# spot-welding.net
KiCad netlist of a schematic drawn in EAGLE
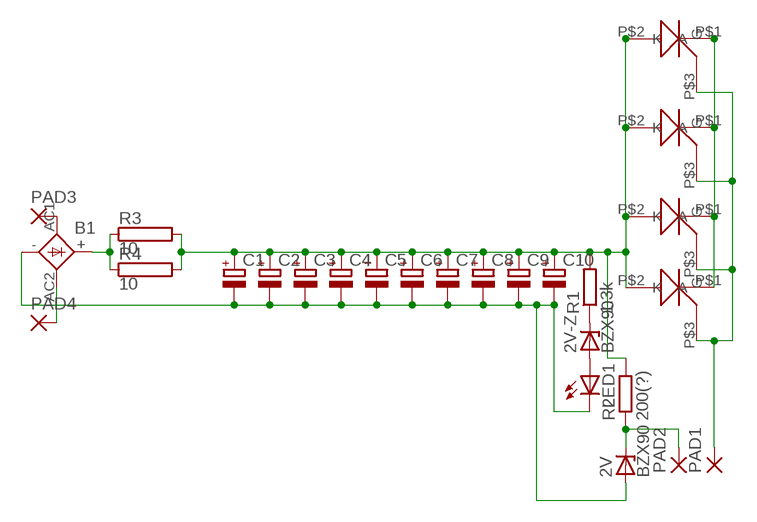
[diagram p0: schematic, sheet 1]

(export (version "E")
  (design (tool "Eeschema 10.0.6"))
  (components
    (comp (ref "2V")
      (value "BZX90")
      (footprint "eagle-import:DO34Z7")
      (libsource (lib "eagle-import") (part "BZX90"))
    )
    (comp (ref "2V-Z")
      (value "BZX90")
      (footprint "eagle-import:DO34Z7")
      (libsource (lib "eagle-import") (part "BZX90"))
    )
    (comp (ref "B1")
      (value "KBU")
      (footprint "eagle-import:KBU")
      (libsource (lib "eagle-import") (part "KBU"))
    )
    (comp (ref "C1")
      (value "CPOL-EUE10-30")
      (footprint "eagle-import:EB30D")
      (libsource (lib "eagle-import") (part "CPOL-EUE10-30"))
    )
    (comp (ref "C2")
      (value "CPOL-EUE10-30")
      (footprint "eagle-import:EB30D")
      (libsource (lib "eagle-import") (part "CPOL-EUE10-30"))
    )
    (comp (ref "C3")
      (value "CPOL-EUE10-30")
      (footprint "eagle-import:EB30D")
      (libsource (lib "eagle-import") (part "CPOL-EUE10-30"))
    )
    (comp (ref "C4")
      (value "CPOL-EUE10-30")
      (footprint "eagle-import:EB30D")
      (libsource (lib "eagle-import") (part "CPOL-EUE10-30"))
    )
    (comp (ref "C5")
      (value "CPOL-EUE10-30")
      (footprint "eagle-import:EB30D")
      (libsource (lib "eagle-import") (part "CPOL-EUE10-30"))
    )
    (comp (ref "C6")
      (value "CPOL-EUE10-30")
      (footprint "eagle-import:EB30D")
      (libsource (lib "eagle-import") (part "CPOL-EUE10-30"))
    )
    (comp (ref "C7")
      (value "CPOL-EUE10-30")
      (footprint "eagle-import:EB30D")
      (libsource (lib "eagle-import") (part "CPOL-EUE10-30"))
    )
    (comp (ref "C8")
      (value "CPOL-EUE10-30")
      (footprint "eagle-import:EB30D")
      (libsource (lib "eagle-import") (part "CPOL-EUE10-30"))
    )
    (comp (ref "C9")
      (value "CPOL-EUE10-30")
      (footprint "eagle-import:EB30D")
      (libsource (lib "eagle-import") (part "CPOL-EUE10-30"))
    )
    (comp (ref "C10")
      (value "CPOL-EUE10-30")
      (footprint "eagle-import:EB30D")
      (libsource (lib "eagle-import") (part "CPOL-EUE10-30"))
    )
    (comp (ref "LED1")
      (value "LED3MM")
      (footprint "eagle-import:LED3MM")
      (libsource (lib "eagle-import") (part "LED3MM"))
    )
    (comp (ref "PAD1")
      (value "3,17/1,1")
      (footprint "eagle-import:3,17_1,1")
      (libsource (lib "eagle-import") (part "3,17/1,1"))
    )
    (comp (ref "PAD2")
      (value "3,17/1,1")
      (footprint "eagle-import:3,17_1,1")
      (libsource (lib "eagle-import") (part "3,17/1,1"))
    )
    (comp (ref "PAD3")
      (value "3,17/1,1")
      (footprint "eagle-import:3,17_1,1")
      (libsource (lib "eagle-import") (part "3,17/1,1"))
    )
    (comp (ref "PAD4")
      (value "3,17/1,1")
      (footprint "eagle-import:3,17_1,1")
      (libsource (lib "eagle-import") (part "3,17/1,1"))
    )
    (comp (ref "R1")
      (value "1.3k")
      (footprint "eagle-import:0204_7")
      (libsource (lib "eagle-import") (part "R-EU_0204/7"))
    )
    (comp (ref "R2")
      (value "200(?)")
      (footprint "eagle-import:0204_7")
      (libsource (lib "eagle-import") (part "R-EU_0204/7"))
    )
    (comp (ref "R3")
      (value "10")
      (footprint "eagle-import:KH214R-8")
      (libsource (lib "eagle-import") (part "RKH214-8R"))
    )
    (comp (ref "R4")
      (value "10")
      (footprint "eagle-import:KH214R-8")
      (libsource (lib "eagle-import") (part "RKH214-8R"))
    )
    (comp (ref "U$1")
      (value "40TPS12")
      (footprint "eagle-import:40TPS12")
      (libsource (lib "eagle-import") (part "40TPS12"))
    )
    (comp (ref "U$2")
      (value "40TPS12")
      (footprint "eagle-import:40TPS12")
      (libsource (lib "eagle-import") (part "40TPS12"))
    )
    (comp (ref "U$3")
      (value "40TPS12")
      (footprint "eagle-import:40TPS12")
      (libsource (lib "eagle-import") (part "40TPS12"))
    )
    (comp (ref "U$4")
      (value "40TPS12")
      (footprint "eagle-import:40TPS12")
      (libsource (lib "eagle-import") (part "40TPS12"))
    )
  )
  (nets
    (net (code "1") (name "Net-(2V-Z-PadA)") (class "Default")
      (node (ref "2V-Z") (pin "A") (pinfunction "A_A") (pintype "passive"))
      (node (ref "LED1") (pin "A") (pinfunction "A_A") (pintype "passive"))
    )
    (net (code "2") (name "Net-(2V-Z-PadC)") (class "Default")
      (node (ref "2V-Z") (pin "C") (pinfunction "C_C") (pintype "passive"))
      (node (ref "R1") (pin "1") (pinfunction "1_1") (pintype "passive"))
    )
    (net (code "3") (name "Net-(B1-Pad+)") (class "Default")
      (node (ref "B1") (pin "+") (pinfunction "+_+") (pintype "passive"))
      (node (ref "R3") (pin "1") (pinfunction "1_1") (pintype "passive"))
      (node (ref "R4") (pin "1") (pinfunction "1_1") (pintype "passive"))
    )
    (net (code "4") (name "Net-(LED1-C)") (class "Default")
      (node (ref "2V") (pin "A") (pinfunction "A_A") (pintype "passive"))
      (node (ref "B1") (pin "-") (pinfunction "-_-") (pintype "passive"))
      (node (ref "C1") (pin "-") (pinfunction "-_-") (pintype "passive"))
      (node (ref "C10") (pin "-") (pinfunction "-_-") (pintype "passive"))
      (node (ref "C2") (pin "-") (pinfunction "-_-") (pintype "passive"))
      (node (ref "C3") (pin "-") (pinfunction "-_-") (pintype "passive"))
      (node (ref "C4") (pin "-") (pinfunction "-_-") (pintype "passive"))
      (node (ref "C5") (pin "-") (pinfunction "-_-") (pintype "passive"))
      (node (ref "C6") (pin "-") (pinfunction "-_-") (pintype "passive"))
      (node (ref "C7") (pin "-") (pinfunction "-_-") (pintype "passive"))
      (node (ref "C8") (pin "-") (pinfunction "-_-") (pintype "passive"))
      (node (ref "C9") (pin "-") (pinfunction "-_-") (pintype "passive"))
      (node (ref "LED1") (pin "K") (pinfunction "C_K") (pintype "passive"))
    )
    (net (code "5") (name "Net-(PAD1-P)") (class "Default")
      (node (ref "PAD1") (pin "1") (pinfunction "P_1") (pintype "passive"))
      (node (ref "U$1") (pin "P$3") (pinfunction "G_P$3") (pintype "bidirectional"))
      (node (ref "U$2") (pin "P$3") (pinfunction "G_P$3") (pintype "bidirectional"))
      (node (ref "U$3") (pin "P$3") (pinfunction "G_P$3") (pintype "bidirectional"))
      (node (ref "U$4") (pin "P$3") (pinfunction "G_P$3") (pintype "bidirectional"))
    )
    (net (code "6") (name "Net-(PAD2-P)") (class "Default")
      (node (ref "2V") (pin "C") (pinfunction "C_C") (pintype "passive"))
      (node (ref "PAD2") (pin "1") (pinfunction "P_1") (pintype "passive"))
      (node (ref "R2") (pin "1") (pinfunction "1_1") (pintype "passive"))
    )
    (net (code "7") (name "Net-(PAD3-P)") (class "Default")
      (node (ref "B1") (pin "AC1") (pinfunction "AC1_AC1") (pintype "passive"))
      (node (ref "PAD3") (pin "1") (pinfunction "P_1") (pintype "passive"))
    )
    (net (code "8") (name "Net-(PAD4-P)") (class "Default")
      (node (ref "B1") (pin "AC2") (pinfunction "AC2_AC2") (pintype "passive"))
      (node (ref "PAD4") (pin "1") (pinfunction "P_1") (pintype "passive"))
    )
    (net (code "9") (name "Net-(U$1-A)") (class "Default")
      (node (ref "C1") (pin "+") (pinfunction "+_+") (pintype "passive"))
      (node (ref "C10") (pin "+") (pinfunction "+_+") (pintype "passive"))
      (node (ref "C2") (pin "+") (pinfunction "+_+") (pintype "passive"))
      (node (ref "C3") (pin "+") (pinfunction "+_+") (pintype "passive"))
      (node (ref "C4") (pin "+") (pinfunction "+_+") (pintype "passive"))
      (node (ref "C5") (pin "+") (pinfunction "+_+") (pintype "passive"))
      (node (ref "C6") (pin "+") (pinfunction "+_+") (pintype "passive"))
      (node (ref "C7") (pin "+") (pinfunction "+_+") (pintype "passive"))
      (node (ref "C8") (pin "+") (pinfunction "+_+") (pintype "passive"))
      (node (ref "C9") (pin "+") (pinfunction "+_+") (pintype "passive"))
      (node (ref "R1") (pin "2") (pinfunction "2_2") (pintype "passive"))
      (node (ref "R2") (pin "2") (pinfunction "2_2") (pintype "passive"))
      (node (ref "R3") (pin "2") (pinfunction "2_2") (pintype "passive"))
      (node (ref "R4") (pin "2") (pinfunction "2_2") (pintype "passive"))
      (node (ref "U$1") (pin "P$2") (pinfunction "A_P$2") (pintype "bidirectional"))
      (node (ref "U$2") (pin "P$2") (pinfunction "A_P$2") (pintype "bidirectional"))
      (node (ref "U$3") (pin "P$2") (pinfunction "A_P$2") (pintype "bidirectional"))
      (node (ref "U$4") (pin "P$2") (pinfunction "A_P$2") (pintype "bidirectional"))
    )
    (net (code "10") (name "Net-(U$1-K)") (class "Default")
      (node (ref "U$1") (pin "P$1") (pinfunction "K_P$1") (pintype "bidirectional"))
      (node (ref "U$2") (pin "P$1") (pinfunction "K_P$1") (pintype "bidirectional"))
      (node (ref "U$3") (pin "P$1") (pinfunction "K_P$1") (pintype "bidirectional"))
      (node (ref "U$4") (pin "P$1") (pinfunction "K_P$1") (pintype "bidirectional"))
    )
  )
)
